# Power.net
KiCad netlist of a schematic drawn in Altium Designer
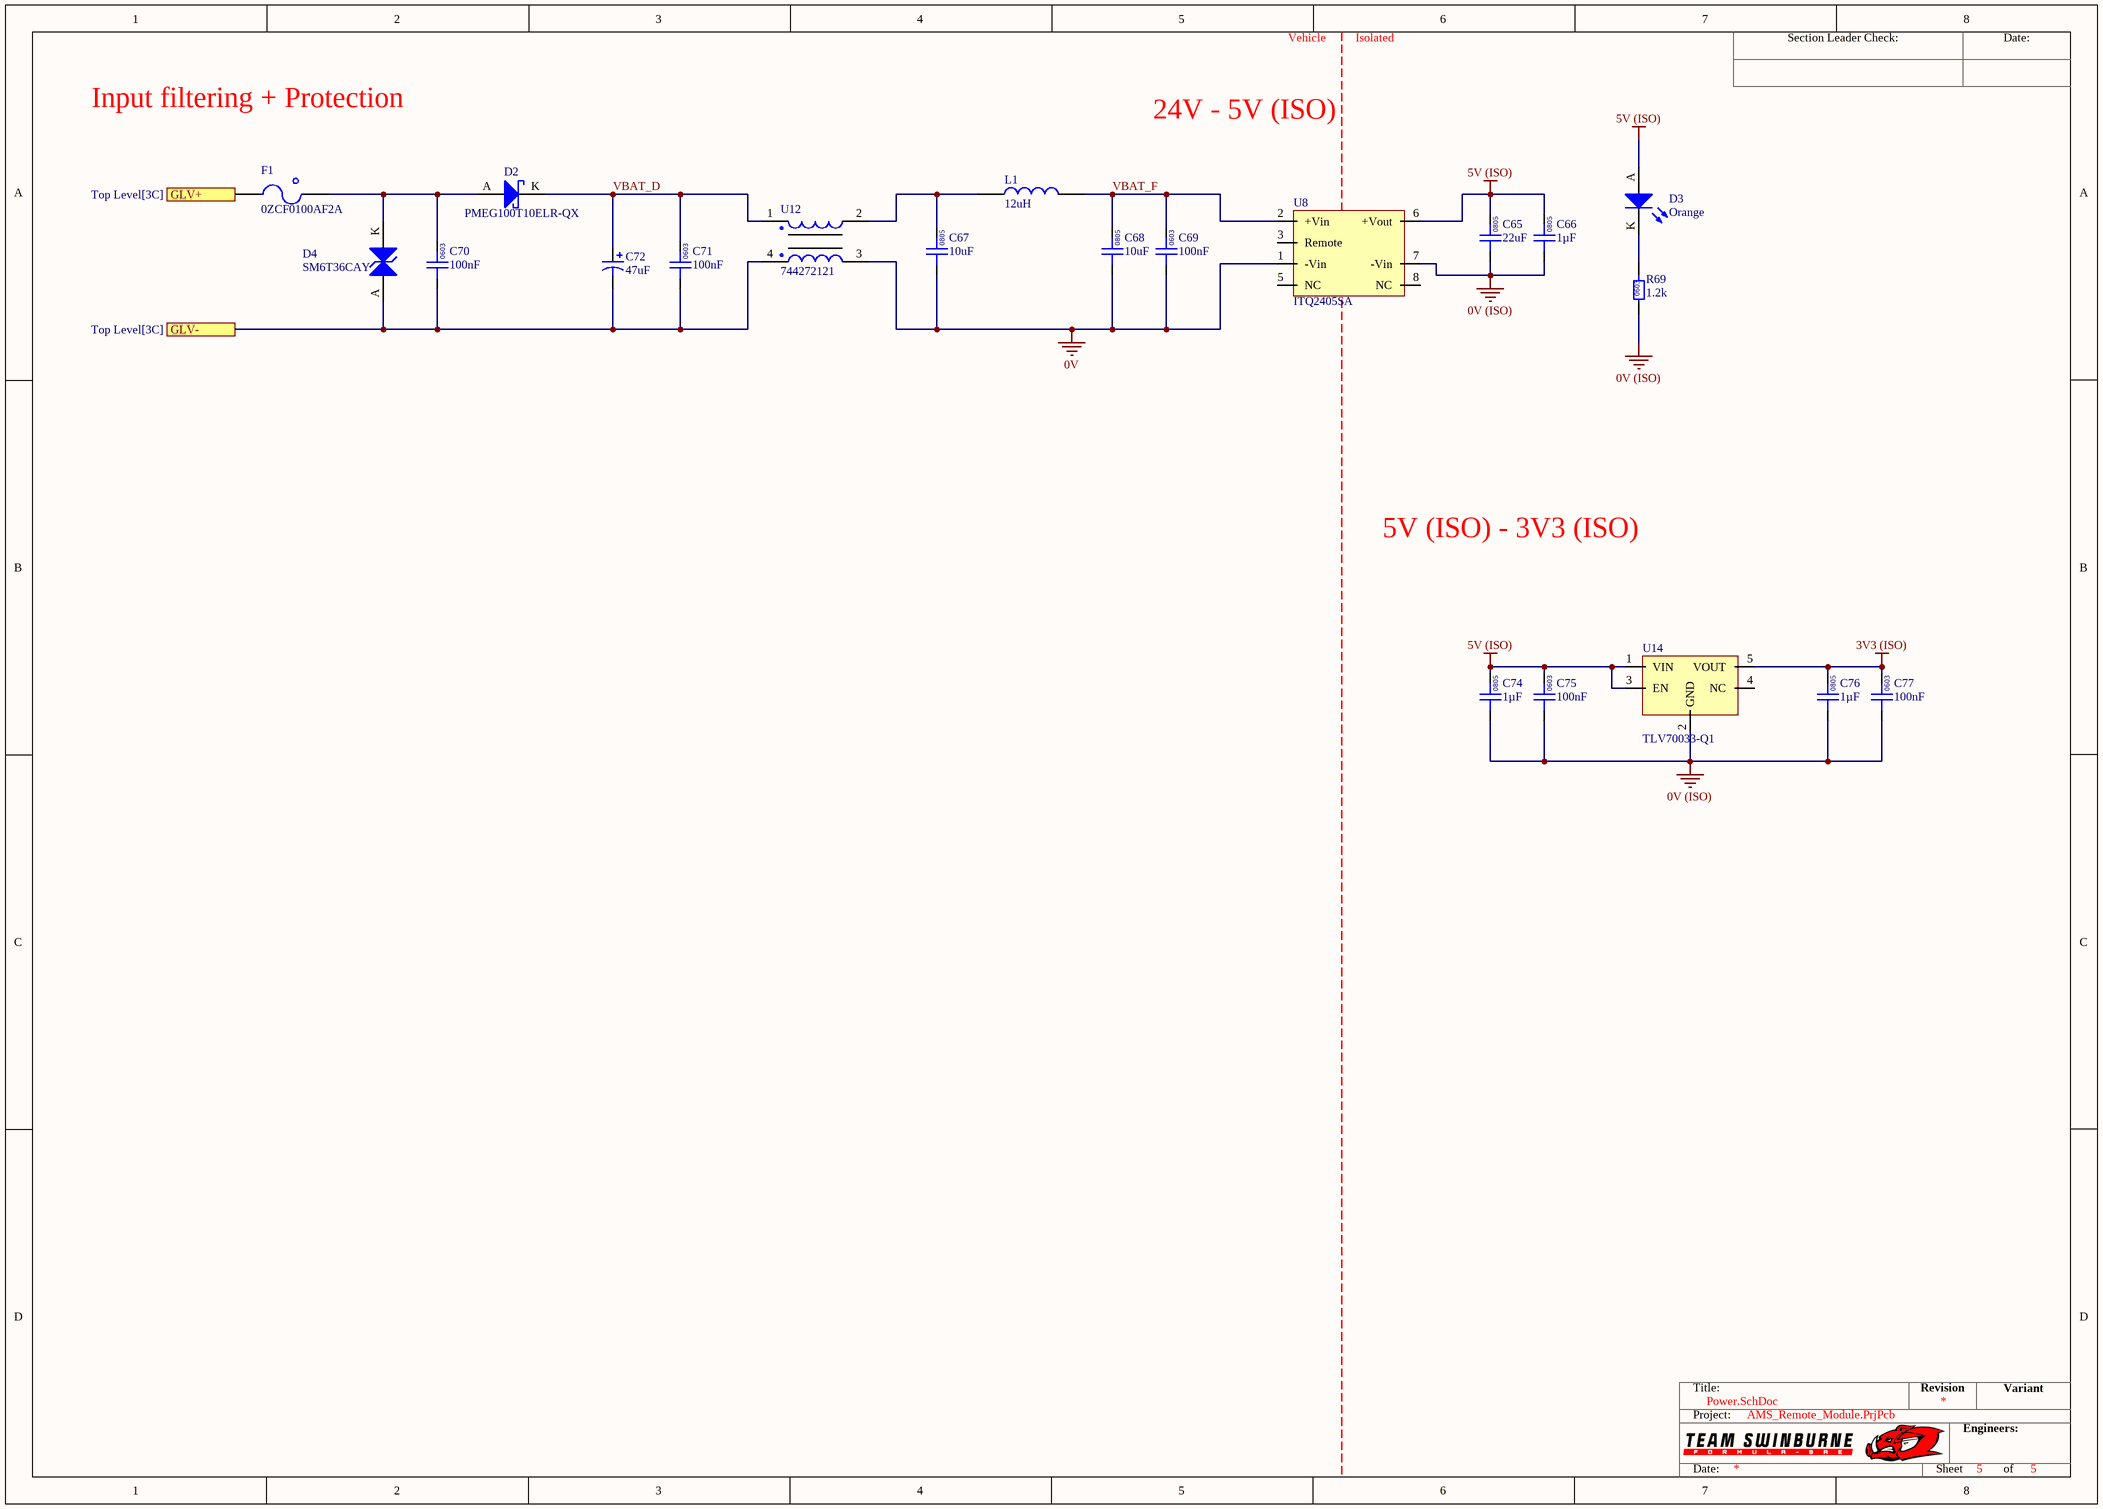
[diagram p0: Power.SchDoc]

(export (version "E")
  (design (tool "Eeschema 10.0.6"))
  (components
    (comp (ref "C65")
      (value "22uF")
      (footprint "0805")
      (fields
        (field (name "PART NUMBER") "GRM21BR61A226ME51L")
        (field (name "MANUFACTURER") "muRata")
        (field (name "TOLERANCE") "20%")
      )
      (libsource (lib "ts_standard_library") (part "Capacitor 0805"))
    )
    (comp (ref "C66")
      (value "1µF")
      (footprint "0805")
      (fields
        (field (name "PART NUMBER") "GCM21BR71H105KA03L")
        (field (name "MANUFACTURER") "muRata")
        (field (name "TOLERANCE") "±10%")
      )
      (libsource (lib "ts_standard_library") (part "Capacitor 0805"))
    )
    (comp (ref "C67")
      (value "10uF")
      (footprint "0805")
      (fields
        (field (name "PART NUMBER") "GRM21BR6YA106KE43L")
        (field (name "MANUFACTURER") "muRata")
        (field (name "TOLERANCE") "10%")
      )
      (libsource (lib "ts_standard_library") (part "Capacitor 0805"))
    )
    (comp (ref "C68")
      (value "10uF")
      (footprint "0805")
      (fields
        (field (name "PART NUMBER") "GRM21BR6YA106KE43L")
        (field (name "MANUFACTURER") "muRata")
        (field (name "TOLERANCE") "10%")
      )
      (libsource (lib "ts_standard_library") (part "Capacitor 0805"))
    )
    (comp (ref "C69")
      (value "100nF")
      (footprint "0603")
      (fields
        (field (name "PART NUMBER") "GCM188L81H104KA57D")
        (field (name "MANUFACTURER") "muRata")
        (field (name "TOLERANCE") "±10%")
      )
      (libsource (lib "ts_standard_library") (part "Capacitor 0603"))
    )
    (comp (ref "C70")
      (value "100nF")
      (footprint "0603")
      (fields
        (field (name "PART NUMBER") "GCM188L81H104KA57D")
        (field (name "MANUFACTURER") "muRata")
        (field (name "TOLERANCE") "±10%")
      )
      (libsource (lib "ts_standard_library") (part "Capacitor 0603"))
    )
    (comp (ref "C71")
      (value "100nF")
      (footprint "0603")
      (fields
        (field (name "PART NUMBER") "GCM188L81H104KA57D")
        (field (name "MANUFACTURER") "muRata")
        (field (name "TOLERANCE") "±10%")
      )
      (libsource (lib "ts_standard_library") (part "Capacitor 0603"))
    )
    (comp (ref "C72")
      (value "~")
      (footprint "CHEMI-CON ELCO")
      (fields
        (field (name "PART NUMBER") "HHXA350ARA470MF61G")
        (field (name "MANUFACTURER") "Chemi-Con")
        (field (name "TOLERANCE") "20%")
      )
      (libsource (lib "ts_standard_library") (part "Capacitor (Polarised)"))
    )
    (comp (ref "C74")
      (value "1µF")
      (footprint "0805")
      (fields
        (field (name "PART NUMBER") "GCM21BR71H105KA03L")
        (field (name "MANUFACTURER") "muRata")
        (field (name "TOLERANCE") "±10%")
      )
      (libsource (lib "ts_standard_library") (part "Capacitor 0805"))
    )
    (comp (ref "C75")
      (value "100nF")
      (footprint "0603")
      (fields
        (field (name "PART NUMBER") "GCM188L81H104KA57D")
        (field (name "MANUFACTURER") "muRata")
        (field (name "TOLERANCE") "±10%")
      )
      (libsource (lib "ts_standard_library") (part "Capacitor 0603"))
    )
    (comp (ref "C76")
      (value "1µF")
      (footprint "0805")
      (fields
        (field (name "PART NUMBER") "GCM21BR71H105KA03L")
        (field (name "MANUFACTURER") "muRata")
        (field (name "TOLERANCE") "±10%")
      )
      (libsource (lib "ts_standard_library") (part "Capacitor 0805"))
    )
    (comp (ref "C77")
      (value "100nF")
      (footprint "0603")
      (fields
        (field (name "PART NUMBER") "GCM188L81H104KA57D")
        (field (name "MANUFACTURER") "muRata")
        (field (name "TOLERANCE") "±10%")
      )
      (libsource (lib "ts_standard_library") (part "Capacitor 0603"))
    )
    (comp (ref "D2")
      (value "PMEG100T10ELR-QX")
      (footprint "NXP SOD123W")
      (fields
        (field (name "MANUFACTURER") "Nexperia USA Inc.")
        (field (name "DIGIKEY PART NUMBER") "1727-PMEG100T10ELR-QXCT-ND")
      )
      (libsource (lib "ts_standard_library") (part "Diode (Schottky)"))
    )
    (comp (ref "D3")
      (value "Orange")
      (footprint "0805 LED")
      (description "Orange LED Indication - Discrete 1.75V 0805 (2012 Metric)")
      (fields (field (name "PART NUMBER") "SML-211DTT86") (field (name "MANUFACTURER") "ROHM Semiconductor"))
      (libsource (lib "ts_standard_library") (part "LED"))
    )
    (comp (ref "D4")
      (value "SM6T36CAY")
      (footprint "ST SMB DIODE")
      (fields
        (field (name "MANUFACTURER") "STMicroelectronics")
        (field (name "DIGIKEY PART NUMBER") "497-10804-1-ND")
      )
      (libsource (lib "ts_standard_library") (part "TVS (Bidirectional)"))
    )
    (comp (ref "F1")
      (value "0ZCF0100AF2A")
      (footprint "2920")
      (description "PTC RESET FUSE 60V 1A 292")
      (fields
        (field (name "MANUFACTURER") "Littelfuse Inc.")
        (field (name "DIGIKEY PART NUMBER") "507-2070-1-ND")
      )
      (libsource (lib "ts_standard_library") (part "PTC Fuse"))
    )
    (comp (ref "L1")
      (value "12uH")
      (footprint "1812")
      (fields
        (field (name "PART NUMBER") "RLS-126")
        (field (name "MANUFACTURER") "Recom")
        (field (name "TOLERANCE") "0.2")
      )
      (libsource (lib "ts_standard_library") (part "Inductor"))
    )
    (comp (ref "R69")
      (value "1.2k")
      (footprint "0603")
      (fields
        (field (name "PART NUMBER") "RC0603JR-071K2L")
        (field (name "MANUFACTURER") "YAGEO")
        (field (name "TOLERANCE") "0.01")
      )
      (libsource (lib "ts_standard_library") (part "Resistor 0603"))
    )
    (comp (ref "U8")
      (value "ITQ2405SA")
      (footprint "8-SIP")
      (description "DC DC CONVERTER 5V 6W")
      (fields (field (name "MANUFACTURER") "XP Power") (field (name "DIGIKEY PART NUMBER") "1470-2858-5-ND"))
      (libsource (lib "ts_standard_library") (part "ITQ2405SA"))
    )
    (comp (ref "U12")
      (value "744272121")
      (footprint "Wurth 4-PC Pad")
      (fields
        (field (name "MANUFACTURER") "Wurth Electronics Inc")
        (field (name "DIGIKEY PART NUMBER") "732-1489-1-ND")
      )
      (libsource (lib "ts_standard_library") (part "CM Choke"))
    )
    (comp (ref "U14")
      (value "TLV70033-Q1")
      (footprint "TI SOT-23-5")
      (description "IC REG LINEAR 3.3V 200MA SOT23-5")
      (fields
        (field (name "MANUFACTURER") "Texas Instruments")
        (field (name "DIGIKEY PART NUMBER") "296-27780-1-ND")
      )
      (libsource (lib "ts_standard_library") (part "TLV70033-Q1"))
    )
  )
  (nets
    (net (code "1") (name "/GLV+") (class "Default")
      (node (ref "F1") (pin "1") (pinfunction "1_1") (pintype "passive"))
    )
    (net (code "2") (name "/GLV-") (class "Default")
      (node (ref "C70") (pin "1") (pinfunction "1_1") (pintype "passive"))
      (node (ref "C71") (pin "1") (pinfunction "1_1") (pintype "passive"))
      (node (ref "C72") (pin "1") (pinfunction "1_1") (pintype "passive"))
      (node (ref "D4") (pin "A") (pinfunction "A_A") (pintype "passive"))
      (node (ref "U12") (pin "4") (pinfunction "4_4") (pintype "passive"))
    )
    (net (code "3") (name "/VBAT_D") (class "Default")
      (node (ref "C71") (pin "2") (pinfunction "2_2") (pintype "passive"))
      (node (ref "C72") (pin "2") (pinfunction "2_2") (pintype "passive"))
      (node (ref "D2") (pin "K") (pinfunction "K_K") (pintype "passive"))
      (node (ref "U12") (pin "1") (pinfunction "1_1") (pintype "passive"))
    )
    (net (code "4") (name "/VBAT_F") (class "Default")
      (node (ref "C68") (pin "2") (pinfunction "2_2") (pintype "passive"))
      (node (ref "C69") (pin "2") (pinfunction "2_2") (pintype "passive"))
      (node (ref "L1") (pin "1") (pinfunction "1_1") (pintype "passive"))
      (node (ref "U8") (pin "2") (pinfunction "+Vin_2") (pintype "passive"))
    )
    (net (code "5") (name "0V") (class "Default")
      (node (ref "C67") (pin "1") (pinfunction "1_1") (pintype "passive"))
      (node (ref "C68") (pin "1") (pinfunction "1_1") (pintype "passive"))
      (node (ref "C69") (pin "1") (pinfunction "1_1") (pintype "passive"))
      (node (ref "U12") (pin "3") (pinfunction "3_3") (pintype "power_in"))
      (node (ref "U8") (pin "1") (pinfunction "-Vin_1") (pintype "passive"))
    )
    (net (code "6") (name "0V (ISO)") (class "Default")
      (node (ref "C65") (pin "1") (pinfunction "1_1") (pintype "passive"))
      (node (ref "C66") (pin "1") (pinfunction "1_1") (pintype "passive"))
      (node (ref "C74") (pin "1") (pinfunction "1_1") (pintype "passive"))
      (node (ref "C75") (pin "1") (pinfunction "1_1") (pintype "passive"))
      (node (ref "C76") (pin "1") (pinfunction "1_1") (pintype "passive"))
      (node (ref "C77") (pin "1") (pinfunction "1_1") (pintype "passive"))
      (node (ref "R69") (pin "1") (pinfunction "1_1") (pintype "passive"))
      (node (ref "U14") (pin "2") (pinfunction "GND_2") (pintype "passive"))
      (node (ref "U8") (pin "7") (pinfunction "-Vin_7") (pintype "passive"))
    )
    (net (code "7") (name "3V3 (ISO)") (class "Default")
      (node (ref "C76") (pin "2") (pinfunction "2_2") (pintype "passive"))
      (node (ref "C77") (pin "2") (pinfunction "2_2") (pintype "passive"))
      (node (ref "U14") (pin "5") (pinfunction "VOUT_5") (pintype "passive"))
    )
    (net (code "8") (name "5V (ISO)") (class "Default")
      (node (ref "C65") (pin "2") (pinfunction "2_2") (pintype "passive"))
      (node (ref "C66") (pin "2") (pinfunction "2_2") (pintype "passive"))
      (node (ref "C74") (pin "2") (pinfunction "2_2") (pintype "passive"))
      (node (ref "C75") (pin "2") (pinfunction "2_2") (pintype "passive"))
      (node (ref "D3") (pin "A") (pinfunction "A_A") (pintype "passive"))
      (node (ref "U14") (pin "1") (pinfunction "VIN_1") (pintype "passive"))
      (node (ref "U14") (pin "3") (pinfunction "EN_3") (pintype "passive"))
      (node (ref "U8") (pin "6") (pinfunction "+Vout_6") (pintype "passive"))
    )
    (net (code "9") (name "Net-(C67-Pad2)") (class "Default")
      (node (ref "C67") (pin "2") (pinfunction "2_2") (pintype "passive"))
      (node (ref "L1") (pin "2") (pinfunction "2_2") (pintype "passive"))
      (node (ref "U12") (pin "2") (pinfunction "2_2") (pintype "passive"))
    )
    (net (code "10") (name "Net-(C70-Pad2)") (class "Default")
      (node (ref "C70") (pin "2") (pinfunction "2_2") (pintype "passive"))
      (node (ref "D2") (pin "A") (pinfunction "A_A") (pintype "passive"))
      (node (ref "D4") (pin "K") (pinfunction "K_K") (pintype "passive"))
      (node (ref "F1") (pin "2") (pinfunction "2_2") (pintype "passive"))
    )
    (net (code "11") (name "Net-(D3-PadK)") (class "Default")
      (node (ref "D3") (pin "K") (pinfunction "K_K") (pintype "passive"))
      (node (ref "R69") (pin "2") (pinfunction "2_2") (pintype "passive"))
    )
    (net (code "12") (name "unconnected-(U8-NC-Pad5)") (class "Default")
      (node (ref "U8") (pin "5") (pinfunction "NC_5") (pintype "passive"))
    )
    (net (code "13") (name "unconnected-(U8-NC-Pad8)") (class "Default")
      (node (ref "U8") (pin "8") (pinfunction "NC_8") (pintype "passive"))
    )
    (net (code "14") (name "unconnected-(U8-Remote-Pad3)") (class "Default")
      (node (ref "U8") (pin "3") (pinfunction "Remote_3") (pintype "passive"))
    )
    (net (code "15") (name "unconnected-(U14-NC-Pad4)") (class "Default")
      (node (ref "U14") (pin "4") (pinfunction "NC_4") (pintype "passive"))
    )
  )
)
